# AD8138.net
KiCad netlist of a schematic drawn in EasyEDA Pro
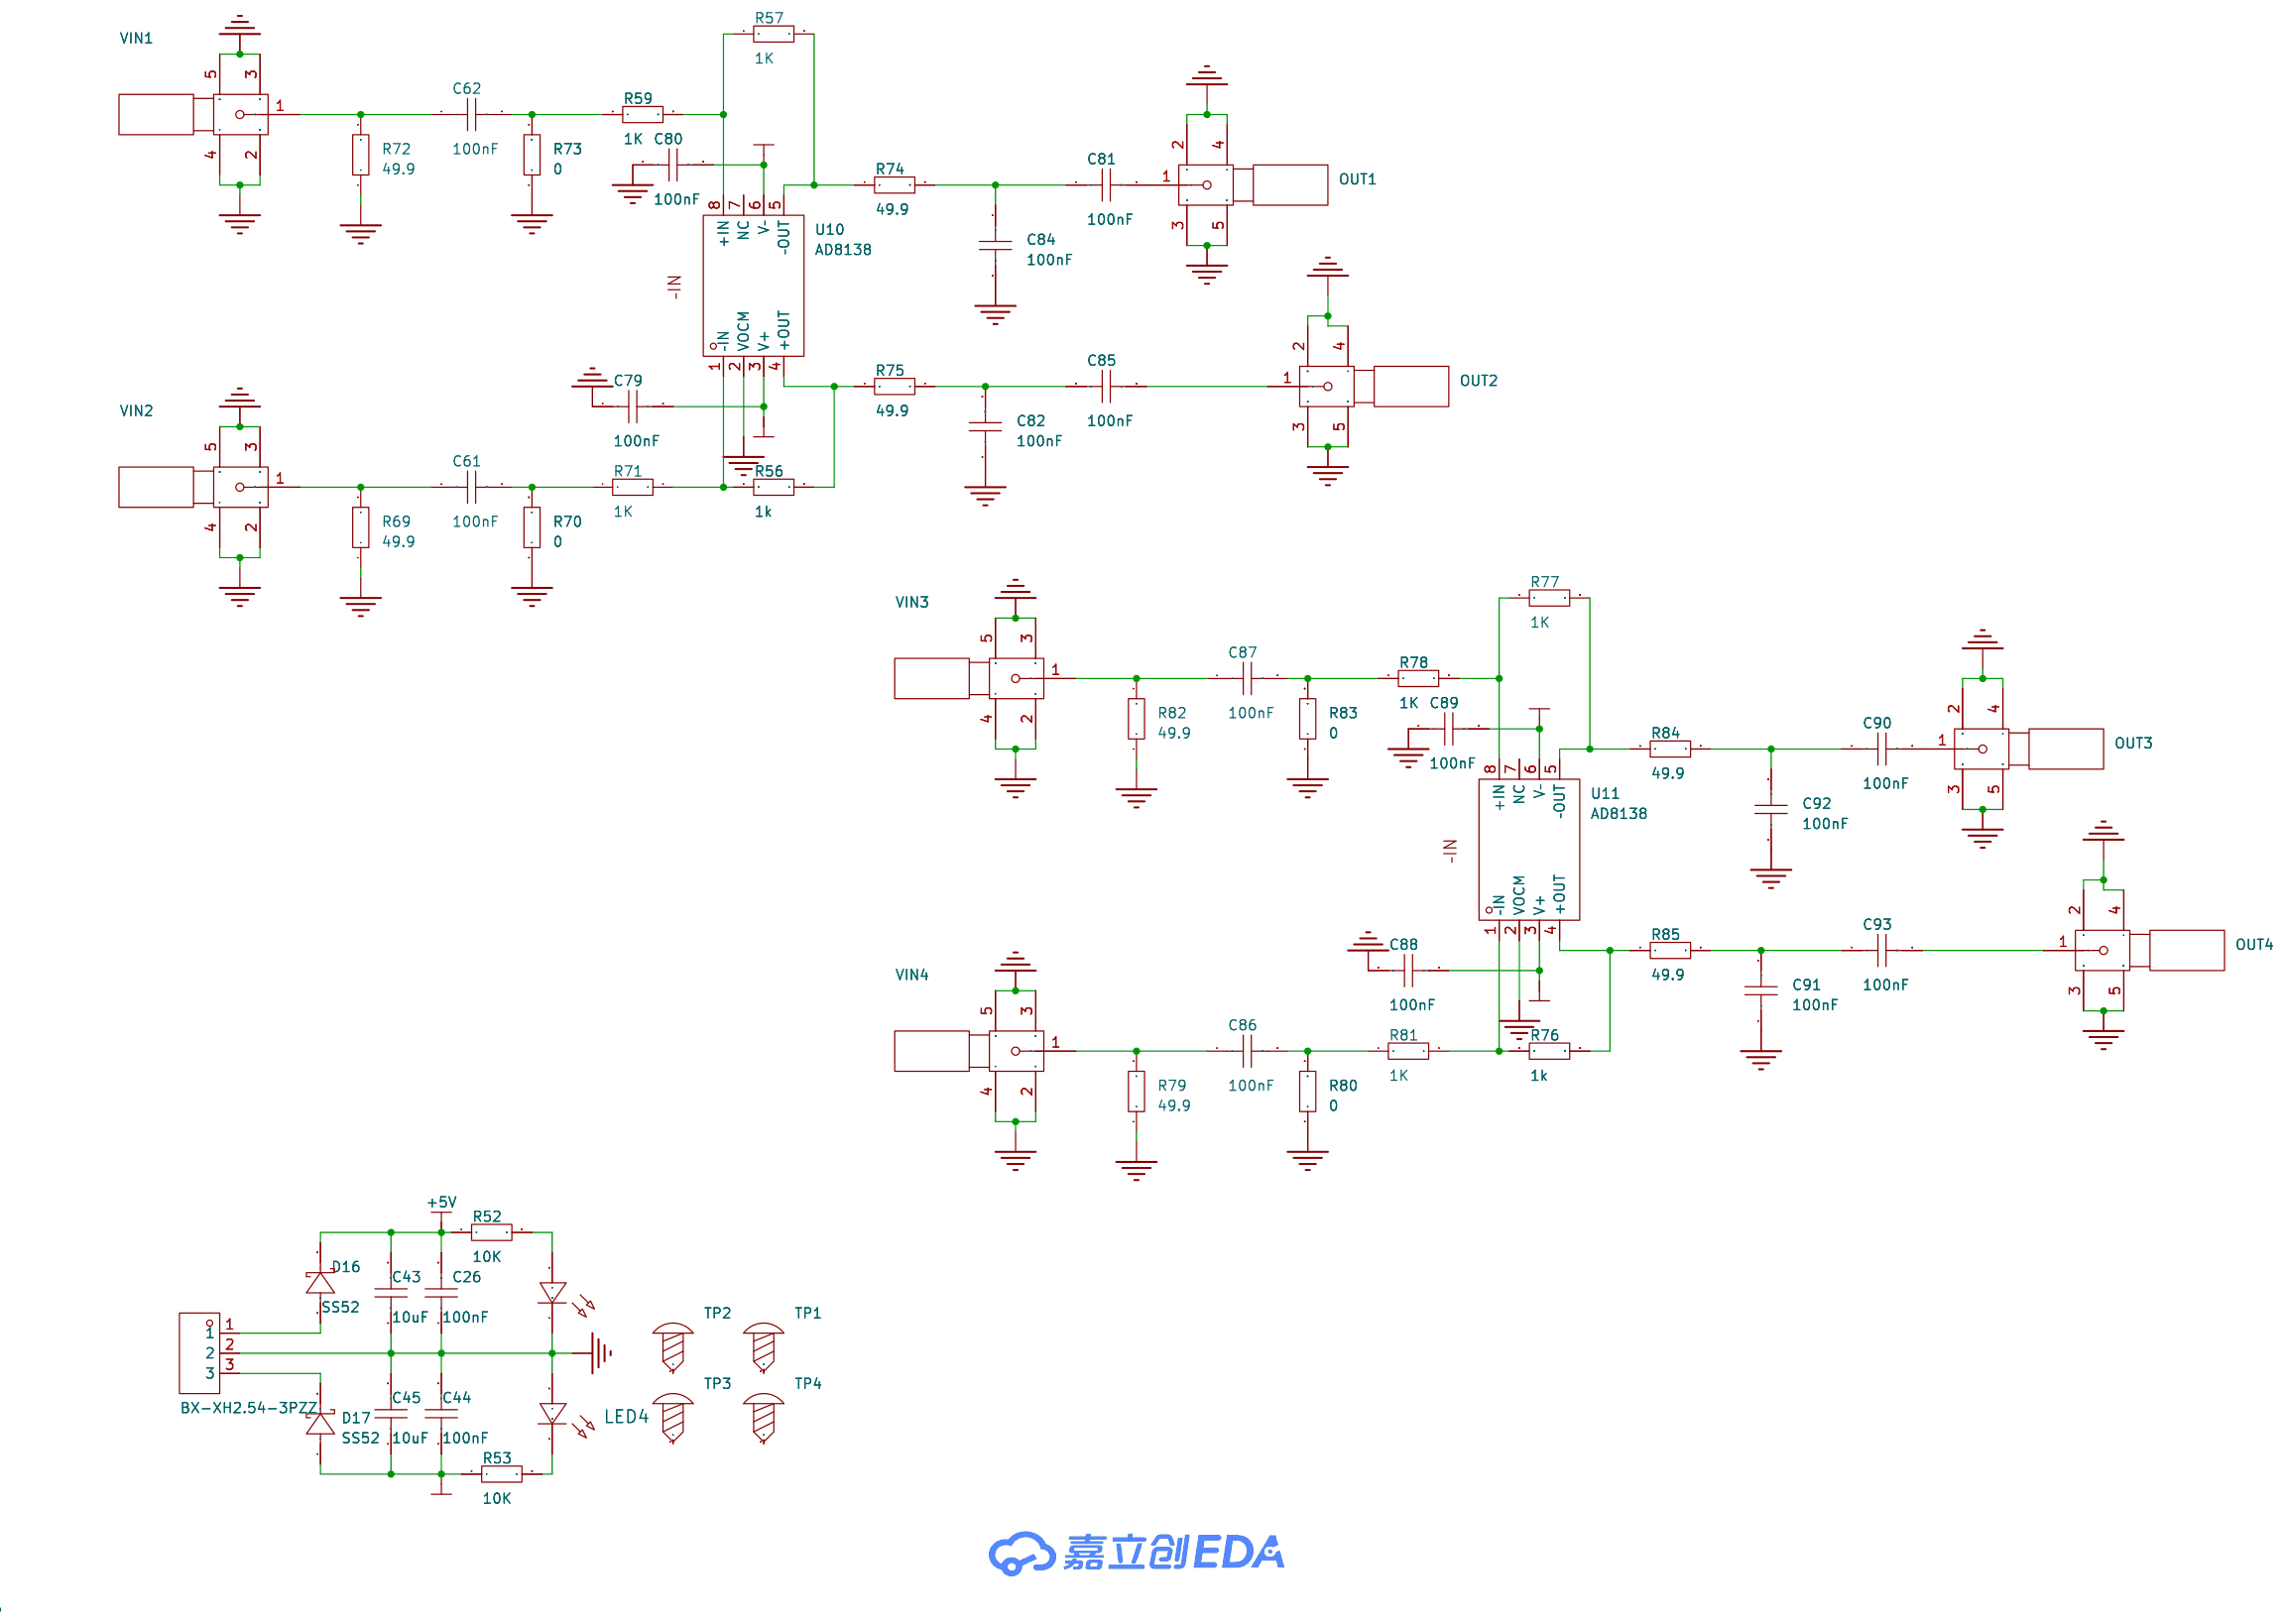
[diagram p0: schematic sheet]

(export (version "E")
  (design (tool "Eeschema 10.0.6"))
  (components
    (comp (ref "C26")
      (value "100nF")
      (footprint "easyedapro:C0603")
      (libsource (lib "easyedapro") (part "CapAcitance"))
    )
    (comp (ref "C43")
      (value "10uF")
      (footprint "easyedapro:C0603")
      (libsource (lib "easyedapro") (part "CapAcitance"))
    )
    (comp (ref "C44")
      (value "100nF")
      (footprint "easyedapro:C0603")
      (libsource (lib "easyedapro") (part "CapAcitance"))
    )
    (comp (ref "C45")
      (value "10uF")
      (footprint "easyedapro:C0603")
      (libsource (lib "easyedapro") (part "CapAcitance"))
    )
    (comp (ref "C61")
      (value "100nF")
      (footprint "easyedapro:C0603")
      (libsource (lib "easyedapro") (part "CapAcitance"))
    )
    (comp (ref "C62")
      (value "100nF")
      (footprint "easyedapro:C0603")
      (libsource (lib "easyedapro") (part "CapAcitance"))
    )
    (comp (ref "C79")
      (value "100nF")
      (footprint "easyedapro:C0603")
      (libsource (lib "easyedapro") (part "CapAcitance"))
    )
    (comp (ref "C80")
      (value "100nF")
      (footprint "easyedapro:C0603")
      (libsource (lib "easyedapro") (part "CapAcitance"))
    )
    (comp (ref "C81")
      (value "100nF")
      (footprint "easyedapro:C0603")
      (libsource (lib "easyedapro") (part "CapAcitance"))
    )
    (comp (ref "C82")
      (value "100nF")
      (footprint "easyedapro:C0603")
      (libsource (lib "easyedapro") (part "CapAcitance"))
    )
    (comp (ref "C84")
      (value "100nF")
      (footprint "easyedapro:C0603")
      (libsource (lib "easyedapro") (part "CapAcitance"))
    )
    (comp (ref "C85")
      (value "100nF")
      (footprint "easyedapro:C0603")
      (libsource (lib "easyedapro") (part "CapAcitance"))
    )
    (comp (ref "C86")
      (value "100nF")
      (footprint "easyedapro:C0603")
      (libsource (lib "easyedapro") (part "CapAcitance"))
    )
    (comp (ref "C87")
      (value "100nF")
      (footprint "easyedapro:C0603")
      (libsource (lib "easyedapro") (part "CapAcitance"))
    )
    (comp (ref "C88")
      (value "100nF")
      (footprint "easyedapro:C0603")
      (libsource (lib "easyedapro") (part "CapAcitance"))
    )
    (comp (ref "C89")
      (value "100nF")
      (footprint "easyedapro:C0603")
      (libsource (lib "easyedapro") (part "CapAcitance"))
    )
    (comp (ref "C90")
      (value "100nF")
      (footprint "easyedapro:C0603")
      (libsource (lib "easyedapro") (part "CapAcitance"))
    )
    (comp (ref "C91")
      (value "100nF")
      (footprint "easyedapro:C0603")
      (libsource (lib "easyedapro") (part "CapAcitance"))
    )
    (comp (ref "C92")
      (value "100nF")
      (footprint "easyedapro:C0603")
      (libsource (lib "easyedapro") (part "CapAcitance"))
    )
    (comp (ref "C93")
      (value "100nF")
      (footprint "easyedapro:C0603")
      (libsource (lib "easyedapro") (part "CapAcitance"))
    )
    (comp (ref "D16")
      (value "SS52")
      (footprint "easyedapro:SMA_L4.3-W2.6-LS5.1-R-RD")
      (description "二极管配置:独立式;正向压降(Vf):550mV@5A;直流反向耐压(Vr):20V;平均整流电流(Io):5A;")
      (fields (field (name "Manufacturer") "TWGMC(台湾迪嘉)"))
      (libsource (lib "easyedapro") (part "SS52_C727064"))
    )
    (comp (ref "D17")
      (value "SS52")
      (footprint "easyedapro:SMA_L4.3-W2.6-LS5.1-R-RD")
      (description "二极管配置:独立式;正向压降(Vf):550mV@5A;直流反向耐压(Vr):20V;平均整流电流(Io):5A;")
      (fields (field (name "Manufacturer") "TWGMC(台湾迪嘉)"))
      (libsource (lib "easyedapro") (part "SS52_C727064"))
    )
    (comp (ref "LED3")
      (value "~")
      (footprint "easyedapro:LED_0603")
      (libsource (lib "easyedapro") (part "LED_R"))
    )
    (comp (ref "LED4")
      (value "~")
      (footprint "easyedapro:LED_0603")
      (libsource (lib "easyedapro") (part "LED_R"))
    )
    (comp (ref "OUT1") (value "被测信号") (libsource (lib "easyedapro") (part "SMA-KE")))
    (comp (ref "OUT2") (value "被测信号") (libsource (lib "easyedapro") (part "SMA-KE")))
    (comp (ref "OUT3") (value "被测信号") (libsource (lib "easyedapro") (part "SMA-KE")))
    (comp (ref "OUT4") (value "被测信号") (libsource (lib "easyedapro") (part "SMA-KE")))
    (comp (ref "R52") (value "10K") (footprint "easyedapro:R0603") (libsource (lib "easyedapro") (part "电阻")))
    (comp (ref "R53") (value "10K") (footprint "easyedapro:R0603") (libsource (lib "easyedapro") (part "电阻")))
    (comp (ref "R56") (value "1k") (footprint "easyedapro:R0603") (libsource (lib "easyedapro") (part "电阻")))
    (comp (ref "R57") (value "1K") (footprint "easyedapro:R0603") (libsource (lib "easyedapro") (part "电阻")))
    (comp (ref "R59") (value "1K") (footprint "easyedapro:R0603") (libsource (lib "easyedapro") (part "电阻")))
    (comp (ref "R69")
      (value "49.9")
      (footprint "easyedapro:R0603")
      (libsource (lib "easyedapro") (part "电阻"))
    )
    (comp (ref "R70") (value "0") (footprint "easyedapro:R0603") (libsource (lib "easyedapro") (part "电阻")))
    (comp (ref "R71") (value "1K") (footprint "easyedapro:R0603") (libsource (lib "easyedapro") (part "电阻")))
    (comp (ref "R72")
      (value "49.9")
      (footprint "easyedapro:R0603")
      (libsource (lib "easyedapro") (part "电阻"))
    )
    (comp (ref "R73") (value "0") (footprint "easyedapro:R0603") (libsource (lib "easyedapro") (part "电阻")))
    (comp (ref "R74")
      (value "49.9")
      (footprint "easyedapro:R0603")
      (libsource (lib "easyedapro") (part "电阻"))
    )
    (comp (ref "R75")
      (value "49.9")
      (footprint "easyedapro:R0603")
      (libsource (lib "easyedapro") (part "电阻"))
    )
    (comp (ref "R76") (value "1k") (footprint "easyedapro:R0603") (libsource (lib "easyedapro") (part "电阻")))
    (comp (ref "R77") (value "1K") (footprint "easyedapro:R0603") (libsource (lib "easyedapro") (part "电阻")))
    (comp (ref "R78") (value "1K") (footprint "easyedapro:R0603") (libsource (lib "easyedapro") (part "电阻")))
    (comp (ref "R79")
      (value "49.9")
      (footprint "easyedapro:R0603")
      (libsource (lib "easyedapro") (part "电阻"))
    )
    (comp (ref "R80") (value "0") (footprint "easyedapro:R0603") (libsource (lib "easyedapro") (part "电阻")))
    (comp (ref "R81") (value "1K") (footprint "easyedapro:R0603") (libsource (lib "easyedapro") (part "电阻")))
    (comp (ref "R82")
      (value "49.9")
      (footprint "easyedapro:R0603")
      (libsource (lib "easyedapro") (part "电阻"))
    )
    (comp (ref "R83") (value "0") (footprint "easyedapro:R0603") (libsource (lib "easyedapro") (part "电阻")))
    (comp (ref "R84")
      (value "49.9")
      (footprint "easyedapro:R0603")
      (libsource (lib "easyedapro") (part "电阻"))
    )
    (comp (ref "R85")
      (value "49.9")
      (footprint "easyedapro:R0603")
      (libsource (lib "easyedapro") (part "电阻"))
    )
    (comp (ref "TP1") (value "~") (footprint "easyedapro:M2螺丝") (libsource (lib "easyedapro") (part "螺丝孔")))
    (comp (ref "TP2") (value "~") (footprint "easyedapro:M2螺丝") (libsource (lib "easyedapro") (part "螺丝孔")))
    (comp (ref "TP3") (value "~") (footprint "easyedapro:M2螺丝") (libsource (lib "easyedapro") (part "螺丝孔")))
    (comp (ref "TP4") (value "~") (footprint "easyedapro:M2螺丝") (libsource (lib "easyedapro") (part "螺丝孔")))
    (comp (ref "U3")
      (value "BX-XH2.54-3PZZ")
      (footprint "easyedapro:CONN-TH_3P-P2.50_BX-XH2.54-3PZZ")
      (fields (field (name "Manufacturer") "Bossie(博锡)"))
      (libsource (lib "easyedapro") (part "BX-XH2.54-3PZZ"))
    )
    (comp (ref "U10")
      (value "AD8138")
      (footprint "easyedapro:SOIC-8_L4.9-W3.9-P1.27-LS6.0-BL")
      (libsource (lib "easyedapro") (part "AD8138"))
    )
    (comp (ref "U11")
      (value "AD8138")
      (footprint "easyedapro:SOIC-8_L4.9-W3.9-P1.27-LS6.0-BL")
      (libsource (lib "easyedapro") (part "AD8138"))
    )
    (comp (ref "VIN1") (value "被测信号") (libsource (lib "easyedapro") (part "SMA-KE")))
    (comp (ref "VIN2") (value "被测信号") (libsource (lib "easyedapro") (part "SMA-KE")))
    (comp (ref "VIN3") (value "被测信号") (libsource (lib "easyedapro") (part "SMA-KE")))
    (comp (ref "VIN4") (value "被测信号") (libsource (lib "easyedapro") (part "SMA-KE")))
  )
  (nets
    (net (code "1") (name "+5V") (class "Default")
      (node (ref "C26") (pin "2") (pinfunction "2_2") (pintype "input"))
      (node (ref "C43") (pin "2") (pinfunction "2_2") (pintype "input"))
      (node (ref "C79") (pin "2") (pinfunction "2_2") (pintype "input"))
      (node (ref "C88") (pin "2") (pinfunction "2_2") (pintype "input"))
      (node (ref "D16") (pin "2") (pinfunction "K_2") (pintype "unspecified"))
      (node (ref "R52") (pin "1") (pinfunction "1_1") (pintype "input"))
      (node (ref "U10") (pin "3") (pinfunction "V+_3") (pintype "unspecified"))
      (node (ref "U11") (pin "3") (pinfunction "V+_3") (pintype "unspecified"))
    )
    (net (code "2") (name "-5V") (class "Default")
      (node (ref "C44") (pin "1") (pinfunction "1_1") (pintype "input"))
      (node (ref "C45") (pin "1") (pinfunction "1_1") (pintype "input"))
      (node (ref "C80") (pin "2") (pinfunction "2_2") (pintype "input"))
      (node (ref "C89") (pin "2") (pinfunction "2_2") (pintype "input"))
      (node (ref "D17") (pin "1") (pinfunction "A_1") (pintype "unspecified"))
      (node (ref "R53") (pin "1") (pinfunction "1_1") (pintype "input"))
      (node (ref "U10") (pin "6") (pinfunction "V–_6") (pintype "unspecified"))
      (node (ref "U11") (pin "6") (pinfunction "V–_6") (pintype "unspecified"))
    )
    (net (code "3") (name "GND") (class "Default")
      (node (ref "C26") (pin "1") (pinfunction "1_1") (pintype "input"))
      (node (ref "C43") (pin "1") (pinfunction "1_1") (pintype "input"))
      (node (ref "C44") (pin "2") (pinfunction "2_2") (pintype "input"))
      (node (ref "C45") (pin "2") (pinfunction "2_2") (pintype "input"))
      (node (ref "C79") (pin "1") (pinfunction "1_1") (pintype "input"))
      (node (ref "C80") (pin "1") (pinfunction "1_1") (pintype "input"))
      (node (ref "C82") (pin "1") (pinfunction "1_1") (pintype "input"))
      (node (ref "C84") (pin "2") (pinfunction "2_2") (pintype "input"))
      (node (ref "C88") (pin "1") (pinfunction "1_1") (pintype "input"))
      (node (ref "C89") (pin "1") (pinfunction "1_1") (pintype "input"))
      (node (ref "C91") (pin "1") (pinfunction "1_1") (pintype "input"))
      (node (ref "C92") (pin "2") (pinfunction "2_2") (pintype "input"))
      (node (ref "LED3") (pin "1") (pinfunction "C_1") (pintype "input"))
      (node (ref "LED4") (pin "2") (pinfunction "A_2") (pintype "input"))
      (node (ref "OUT1") (pin "2") (pinfunction "2_2") (pintype "input"))
      (node (ref "OUT1") (pin "3") (pinfunction "3_3") (pintype "input"))
      (node (ref "OUT1") (pin "4") (pinfunction "4_4") (pintype "input"))
      (node (ref "OUT1") (pin "5") (pinfunction "5_5") (pintype "input"))
      (node (ref "OUT2") (pin "2") (pinfunction "2_2") (pintype "input"))
      (node (ref "OUT2") (pin "3") (pinfunction "3_3") (pintype "input"))
      (node (ref "OUT2") (pin "4") (pinfunction "4_4") (pintype "input"))
      (node (ref "OUT2") (pin "5") (pinfunction "5_5") (pintype "input"))
      (node (ref "OUT3") (pin "2") (pinfunction "2_2") (pintype "input"))
      (node (ref "OUT3") (pin "3") (pinfunction "3_3") (pintype "input"))
      (node (ref "OUT3") (pin "4") (pinfunction "4_4") (pintype "input"))
      (node (ref "OUT3") (pin "5") (pinfunction "5_5") (pintype "input"))
      (node (ref "OUT4") (pin "2") (pinfunction "2_2") (pintype "input"))
      (node (ref "OUT4") (pin "3") (pinfunction "3_3") (pintype "input"))
      (node (ref "OUT4") (pin "4") (pinfunction "4_4") (pintype "input"))
      (node (ref "OUT4") (pin "5") (pinfunction "5_5") (pintype "input"))
      (node (ref "R69") (pin "1") (pinfunction "1_1") (pintype "input"))
      (node (ref "R70") (pin "1") (pinfunction "1_1") (pintype "input"))
      (node (ref "R72") (pin "1") (pinfunction "1_1") (pintype "input"))
      (node (ref "R73") (pin "1") (pinfunction "1_1") (pintype "input"))
      (node (ref "R79") (pin "1") (pinfunction "1_1") (pintype "input"))
      (node (ref "R80") (pin "1") (pinfunction "1_1") (pintype "input"))
      (node (ref "R82") (pin "1") (pinfunction "1_1") (pintype "input"))
      (node (ref "R83") (pin "1") (pinfunction "1_1") (pintype "input"))
      (node (ref "U10") (pin "2") (pinfunction "VOCM_2") (pintype "unspecified"))
      (node (ref "U11") (pin "2") (pinfunction "VOCM_2") (pintype "unspecified"))
      (node (ref "U3") (pin "2") (pinfunction "2_2") (pintype "unspecified"))
      (node (ref "VIN1") (pin "2") (pinfunction "2_2") (pintype "input"))
      (node (ref "VIN1") (pin "3") (pinfunction "3_3") (pintype "input"))
      (node (ref "VIN1") (pin "4") (pinfunction "4_4") (pintype "input"))
      (node (ref "VIN1") (pin "5") (pinfunction "5_5") (pintype "input"))
      (node (ref "VIN2") (pin "2") (pinfunction "2_2") (pintype "input"))
      (node (ref "VIN2") (pin "3") (pinfunction "3_3") (pintype "input"))
      (node (ref "VIN2") (pin "4") (pinfunction "4_4") (pintype "input"))
      (node (ref "VIN2") (pin "5") (pinfunction "5_5") (pintype "input"))
      (node (ref "VIN3") (pin "2") (pinfunction "2_2") (pintype "input"))
      (node (ref "VIN3") (pin "3") (pinfunction "3_3") (pintype "input"))
      (node (ref "VIN3") (pin "4") (pinfunction "4_4") (pintype "input"))
      (node (ref "VIN3") (pin "5") (pinfunction "5_5") (pintype "input"))
      (node (ref "VIN4") (pin "2") (pinfunction "2_2") (pintype "input"))
      (node (ref "VIN4") (pin "3") (pinfunction "3_3") (pintype "input"))
      (node (ref "VIN4") (pin "4") (pinfunction "4_4") (pintype "input"))
      (node (ref "VIN4") (pin "5") (pinfunction "5_5") (pintype "input"))
    )
    (net (code "4") (name "Net-(C61-Pad1)") (class "Default")
      (node (ref "C61") (pin "1") (pinfunction "1_1") (pintype "input"))
      (node (ref "R69") (pin "2") (pinfunction "2_2") (pintype "input"))
      (node (ref "VIN2") (pin "1") (pinfunction "1_1") (pintype "input"))
    )
    (net (code "5") (name "Net-(C61-Pad2)") (class "Default")
      (node (ref "C61") (pin "2") (pinfunction "2_2") (pintype "input"))
      (node (ref "R70") (pin "2") (pinfunction "2_2") (pintype "input"))
      (node (ref "R71") (pin "1") (pinfunction "1_1") (pintype "input"))
    )
    (net (code "6") (name "Net-(C62-Pad1)") (class "Default")
      (node (ref "C62") (pin "1") (pinfunction "1_1") (pintype "input"))
      (node (ref "R72") (pin "2") (pinfunction "2_2") (pintype "input"))
      (node (ref "VIN1") (pin "1") (pinfunction "1_1") (pintype "input"))
    )
    (net (code "7") (name "Net-(C62-Pad2)") (class "Default")
      (node (ref "C62") (pin "2") (pinfunction "2_2") (pintype "input"))
      (node (ref "R59") (pin "1") (pinfunction "1_1") (pintype "input"))
      (node (ref "R73") (pin "2") (pinfunction "2_2") (pintype "input"))
    )
    (net (code "8") (name "Net-(C81-Pad1)") (class "Default")
      (node (ref "C81") (pin "1") (pinfunction "1_1") (pintype "input"))
      (node (ref "C84") (pin "1") (pinfunction "1_1") (pintype "input"))
      (node (ref "R74") (pin "2") (pinfunction "2_2") (pintype "input"))
    )
    (net (code "9") (name "Net-(C81-Pad2)") (class "Default")
      (node (ref "C81") (pin "2") (pinfunction "2_2") (pintype "input"))
      (node (ref "OUT1") (pin "1") (pinfunction "1_1") (pintype "input"))
    )
    (net (code "10") (name "Net-(C82-Pad2)") (class "Default")
      (node (ref "C82") (pin "2") (pinfunction "2_2") (pintype "input"))
      (node (ref "C85") (pin "1") (pinfunction "1_1") (pintype "input"))
      (node (ref "R75") (pin "2") (pinfunction "2_2") (pintype "input"))
    )
    (net (code "11") (name "Net-(C85-Pad2)") (class "Default")
      (node (ref "C85") (pin "2") (pinfunction "2_2") (pintype "input"))
      (node (ref "OUT2") (pin "1") (pinfunction "1_1") (pintype "input"))
    )
    (net (code "12") (name "Net-(C86-Pad1)") (class "Default")
      (node (ref "C86") (pin "1") (pinfunction "1_1") (pintype "input"))
      (node (ref "R79") (pin "2") (pinfunction "2_2") (pintype "input"))
      (node (ref "VIN4") (pin "1") (pinfunction "1_1") (pintype "input"))
    )
    (net (code "13") (name "Net-(C86-Pad2)") (class "Default")
      (node (ref "C86") (pin "2") (pinfunction "2_2") (pintype "input"))
      (node (ref "R80") (pin "2") (pinfunction "2_2") (pintype "input"))
      (node (ref "R81") (pin "1") (pinfunction "1_1") (pintype "input"))
    )
    (net (code "14") (name "Net-(C87-Pad1)") (class "Default")
      (node (ref "C87") (pin "1") (pinfunction "1_1") (pintype "input"))
      (node (ref "R82") (pin "2") (pinfunction "2_2") (pintype "input"))
      (node (ref "VIN3") (pin "1") (pinfunction "1_1") (pintype "input"))
    )
    (net (code "15") (name "Net-(C87-Pad2)") (class "Default")
      (node (ref "C87") (pin "2") (pinfunction "2_2") (pintype "input"))
      (node (ref "R78") (pin "1") (pinfunction "1_1") (pintype "input"))
      (node (ref "R83") (pin "2") (pinfunction "2_2") (pintype "input"))
    )
    (net (code "16") (name "Net-(C90-Pad1)") (class "Default")
      (node (ref "C90") (pin "1") (pinfunction "1_1") (pintype "input"))
      (node (ref "C92") (pin "1") (pinfunction "1_1") (pintype "input"))
      (node (ref "R84") (pin "2") (pinfunction "2_2") (pintype "input"))
    )
    (net (code "17") (name "Net-(C90-Pad2)") (class "Default")
      (node (ref "C90") (pin "2") (pinfunction "2_2") (pintype "input"))
      (node (ref "OUT3") (pin "1") (pinfunction "1_1") (pintype "input"))
    )
    (net (code "18") (name "Net-(C91-Pad2)") (class "Default")
      (node (ref "C91") (pin "2") (pinfunction "2_2") (pintype "input"))
      (node (ref "C93") (pin "1") (pinfunction "1_1") (pintype "input"))
      (node (ref "R85") (pin "2") (pinfunction "2_2") (pintype "input"))
    )
    (net (code "19") (name "Net-(C93-Pad2)") (class "Default")
      (node (ref "C93") (pin "2") (pinfunction "2_2") (pintype "input"))
      (node (ref "OUT4") (pin "1") (pinfunction "1_1") (pintype "input"))
    )
    (net (code "20") (name "Net-(D16-A)") (class "Default")
      (node (ref "D16") (pin "1") (pinfunction "A_1") (pintype "unspecified"))
      (node (ref "U3") (pin "1") (pinfunction "1_1") (pintype "unspecified"))
    )
    (net (code "21") (name "Net-(D17-K)") (class "Default")
      (node (ref "D17") (pin "2") (pinfunction "K_2") (pintype "unspecified"))
      (node (ref "U3") (pin "3") (pinfunction "3_3") (pintype "unspecified"))
    )
    (net (code "22") (name "Net-(LED3-A)") (class "Default")
      (node (ref "LED3") (pin "2") (pinfunction "A_2") (pintype "input"))
      (node (ref "R52") (pin "2") (pinfunction "2_2") (pintype "input"))
    )
    (net (code "23") (name "Net-(LED4-C)") (class "Default")
      (node (ref "LED4") (pin "1") (pinfunction "C_1") (pintype "input"))
      (node (ref "R53") (pin "2") (pinfunction "2_2") (pintype "input"))
    )
    (net (code "24") (name "Net-(U10-+IN)") (class "Default")
      (node (ref "R57") (pin "1") (pinfunction "1_1") (pintype "input"))
      (node (ref "R59") (pin "2") (pinfunction "2_2") (pintype "input"))
      (node (ref "U10") (pin "8") (pinfunction "+IN_8") (pintype "unspecified"))
    )
    (net (code "25") (name "Net-(U10-+OUT)") (class "Default")
      (node (ref "R56") (pin "2") (pinfunction "2_2") (pintype "input"))
      (node (ref "R75") (pin "1") (pinfunction "1_1") (pintype "input"))
      (node (ref "U10") (pin "4") (pinfunction "+OUT_4") (pintype "unspecified"))
    )
    (net (code "26") (name "Net-(U10-–IN)") (class "Default")
      (node (ref "R56") (pin "1") (pinfunction "1_1") (pintype "input"))
      (node (ref "R71") (pin "2") (pinfunction "2_2") (pintype "input"))
      (node (ref "U10") (pin "1") (pinfunction "–IN_1") (pintype "unspecified"))
    )
    (net (code "27") (name "Net-(U10-–OUT)") (class "Default")
      (node (ref "R57") (pin "2") (pinfunction "2_2") (pintype "input"))
      (node (ref "R74") (pin "1") (pinfunction "1_1") (pintype "input"))
      (node (ref "U10") (pin "5") (pinfunction "–OUT_5") (pintype "unspecified"))
    )
    (net (code "28") (name "Net-(U11-+IN)") (class "Default")
      (node (ref "R77") (pin "1") (pinfunction "1_1") (pintype "input"))
      (node (ref "R78") (pin "2") (pinfunction "2_2") (pintype "input"))
      (node (ref "U11") (pin "8") (pinfunction "+IN_8") (pintype "unspecified"))
    )
    (net (code "29") (name "Net-(U11-+OUT)") (class "Default")
      (node (ref "R76") (pin "2") (pinfunction "2_2") (pintype "input"))
      (node (ref "R85") (pin "1") (pinfunction "1_1") (pintype "input"))
      (node (ref "U11") (pin "4") (pinfunction "+OUT_4") (pintype "unspecified"))
    )
    (net (code "30") (name "Net-(U11-–IN)") (class "Default")
      (node (ref "R76") (pin "1") (pinfunction "1_1") (pintype "input"))
      (node (ref "R81") (pin "2") (pinfunction "2_2") (pintype "input"))
      (node (ref "U11") (pin "1") (pinfunction "–IN_1") (pintype "unspecified"))
    )
    (net (code "31") (name "Net-(U11-–OUT)") (class "Default")
      (node (ref "R77") (pin "2") (pinfunction "2_2") (pintype "input"))
      (node (ref "R84") (pin "1") (pinfunction "1_1") (pintype "input"))
      (node (ref "U11") (pin "5") (pinfunction "–OUT_5") (pintype "unspecified"))
    )
    (net (code "32") (name "unconnected-(TP1-Pad1)") (class "Default")
      (node (ref "TP1") (pin "1") (pinfunction "1_1") (pintype "input"))
    )
    (net (code "33") (name "unconnected-(TP2-Pad1)") (class "Default")
      (node (ref "TP2") (pin "1") (pinfunction "1_1") (pintype "input"))
    )
    (net (code "34") (name "unconnected-(TP3-Pad1)") (class "Default")
      (node (ref "TP3") (pin "1") (pinfunction "1_1") (pintype "input"))
    )
    (net (code "35") (name "unconnected-(TP4-Pad1)") (class "Default")
      (node (ref "TP4") (pin "1") (pinfunction "1_1") (pintype "input"))
    )
    (net (code "36") (name "unconnected-(U10-NC-Pad7)") (class "Default")
      (node (ref "U10") (pin "7") (pinfunction "NC_7") (pintype "unspecified"))
    )
    (net (code "37") (name "unconnected-(U11-NC-Pad7)") (class "Default")
      (node (ref "U11") (pin "7") (pinfunction "NC_7") (pintype "unspecified"))
    )
  )
)
